# IPMC_UnderTesting.net
KiCad netlist of a schematic drawn in Altium Designer
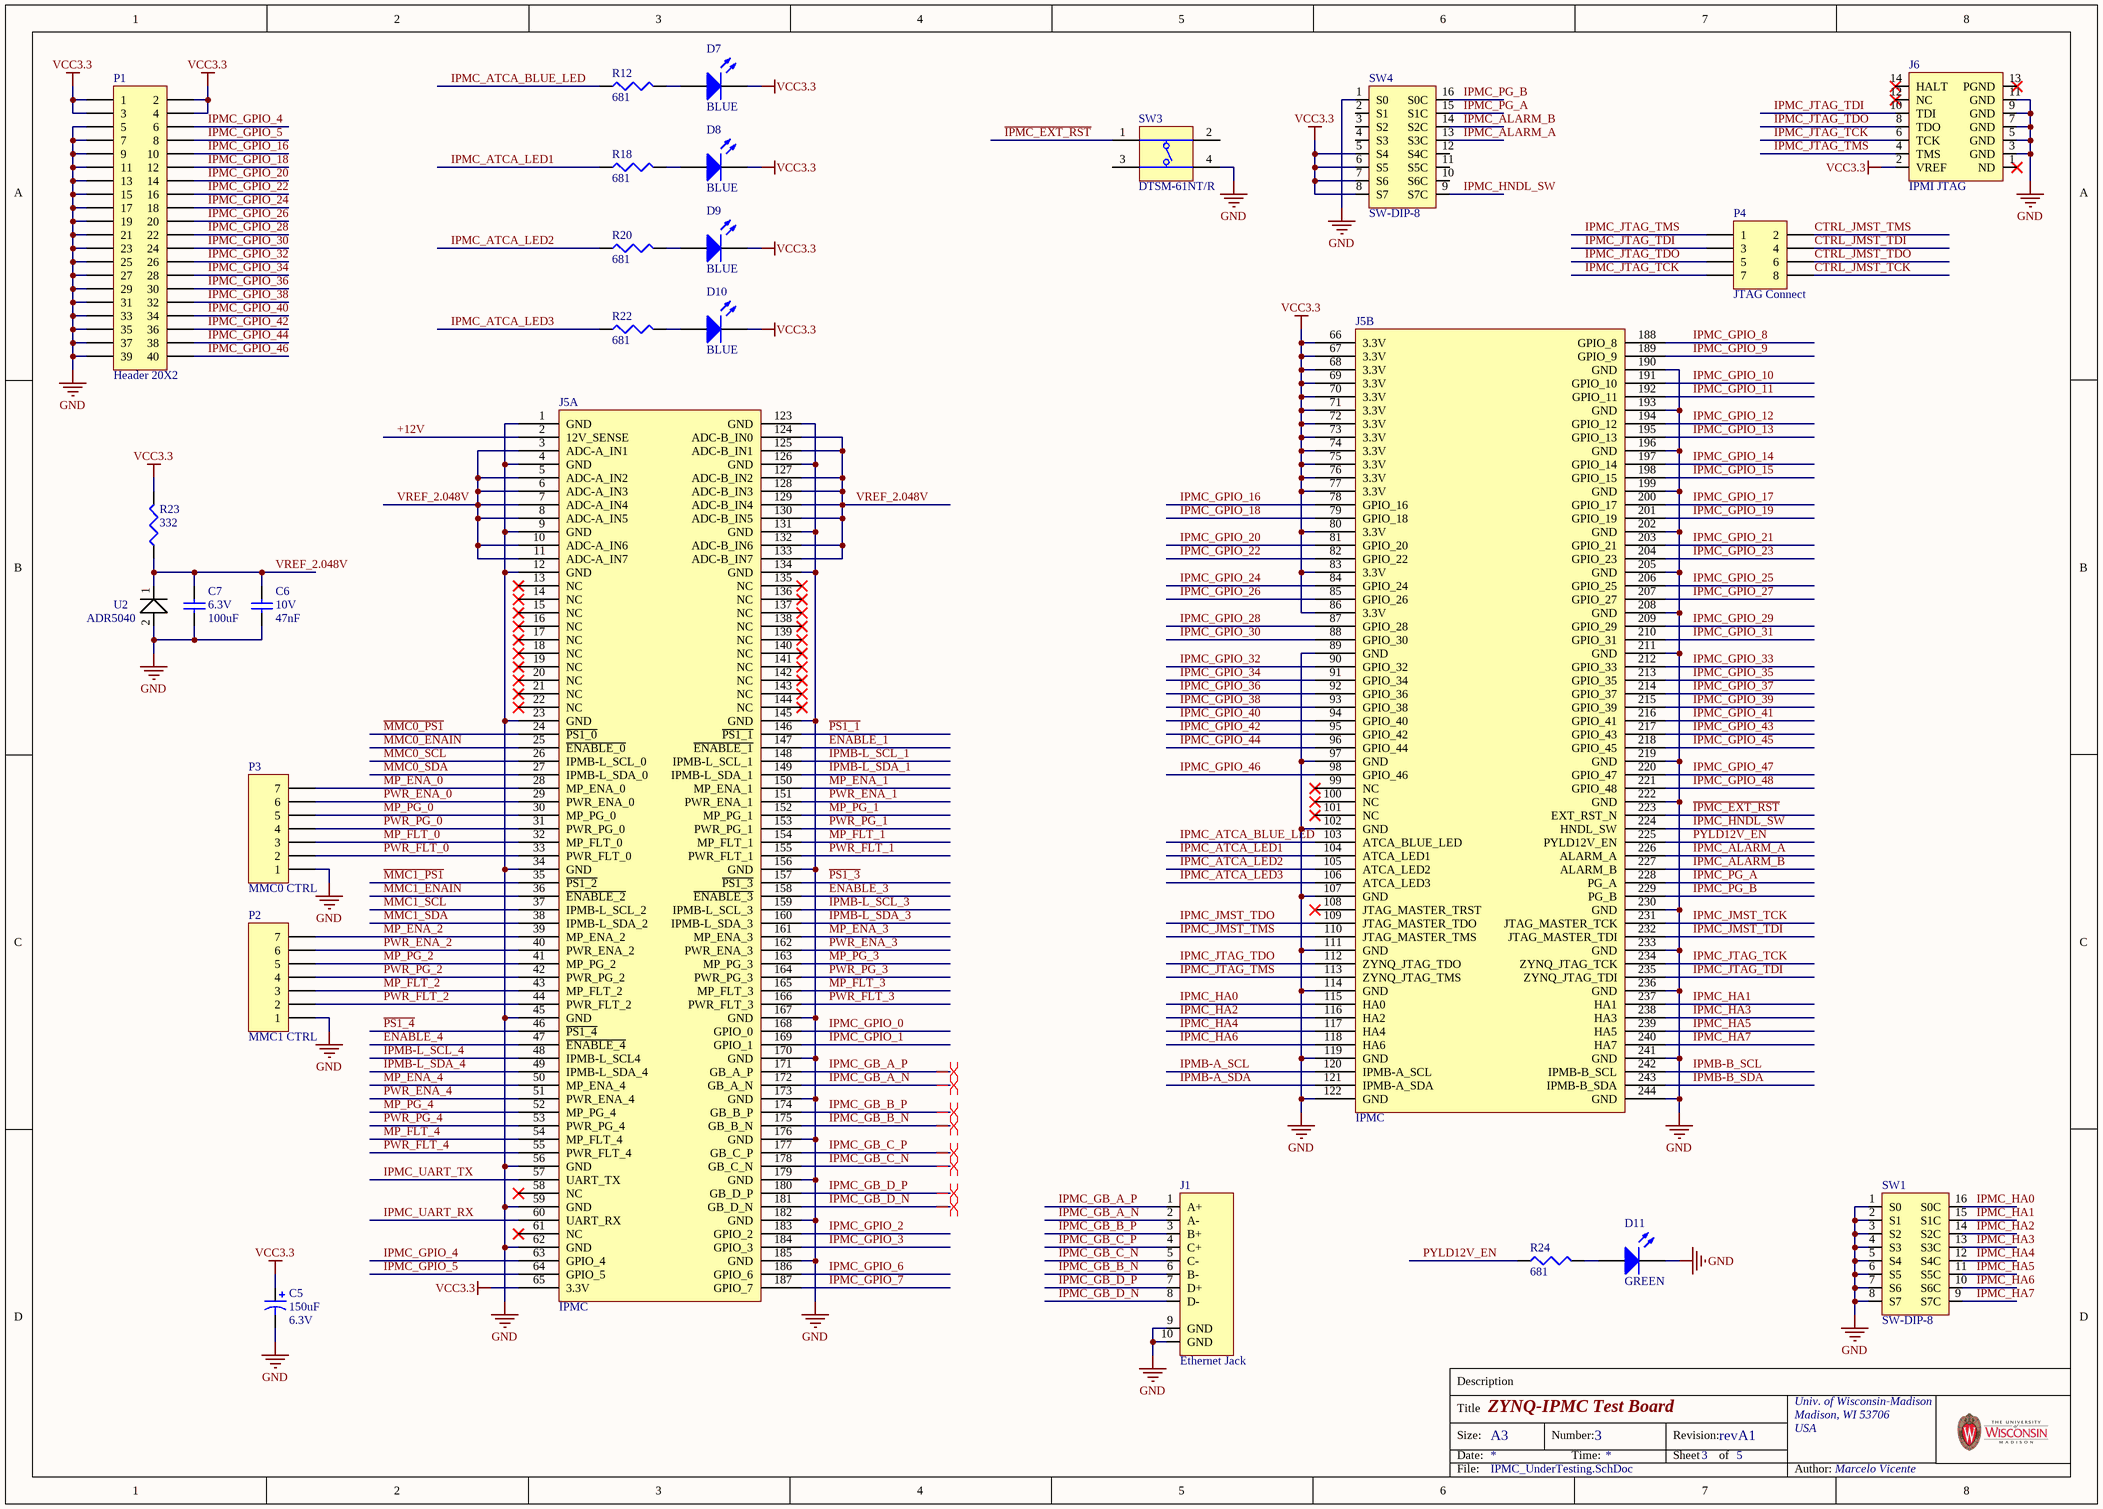
[diagram p0: IPMC_UnderTesting.SchDoc]

(export (version "E")
  (design (tool "Eeschema 10.0.6"))
  (components
    (comp (ref "C5")
      (value "150uF")
      (footprint "VISH-293D-7343-31_V")
      (description "Polarized Capacitor (Surface Mount)")
      (fields
        (field (name "RATING") "6.3V")
        (field (name "MFG. PART NO.") "A700X157M006ATE015")
        (field (name "Comment") "?")
      )
      (libsource (lib "Miscellaneous Devices") (part "Cap Pol3"))
    )
    (comp (ref "C6")
      (value "47nF")
      (footprint "C0402_IPC_H")
      (description "Capacitor")
      (fields
        (field (name "RATING") "10V")
        (field (name "MFG. PART NO.") "ECJ-0EB1A473K")
        (field (name "Comment") "?")
      )
      (libsource (lib "CustomSymbols") (part "Cap"))
    )
    (comp (ref "C7")
      (value "100uF")
      (footprint "C1210_IPC_H")
      (description "Capacitor")
      (fields
        (field (name "RATING") "6.3V")
        (field (name "MFG. PART NO.") "GRM32ER60J107ME20L")
        (field (name "Comment") "?")
      )
      (libsource (lib "CustomSymbols") (part "Cap"))
    )
    (comp (ref "D7")
      (value "BLUE")
      (footprint "LED0603_M")
      (description "Light Emitting Diode")
      (fields (field (name "MFG. PART NO.") "LTST-S270TBKT"))
      (libsource (lib "CustomSymbols") (part "LED"))
    )
    (comp (ref "D8")
      (value "BLUE")
      (footprint "LED0603_M")
      (description "Light Emitting Diode")
      (fields (field (name "MFG. PART NO.") "LTST-S270TBKT"))
      (libsource (lib "CustomSymbols") (part "LED"))
    )
    (comp (ref "D9")
      (value "BLUE")
      (footprint "LED0603_M")
      (description "Light Emitting Diode")
      (fields (field (name "MFG. PART NO.") "LTST-S270TBKT"))
      (libsource (lib "CustomSymbols") (part "LED"))
    )
    (comp (ref "D10")
      (value "BLUE")
      (footprint "LED0603_M")
      (description "Light Emitting Diode")
      (fields (field (name "MFG. PART NO.") "LTST-S270TBKT"))
      (libsource (lib "CustomSymbols") (part "LED"))
    )
    (comp (ref "D11")
      (value "GREEN")
      (footprint "LED0603_M")
      (description "Light Emitting Diode")
      (fields (field (name "MFG. PART NO.") "LTST-S270KGKT"))
      (libsource (lib "CustomSymbols") (part "LED"))
    )
    (comp (ref "J1")
      (value "Ethernet Jack")
      (footprint "43202-8916")
      (description "RJ45 Ethernet Jack")
      (fields (field (name "MFG. PART NO.") "43202-8916"))
      (libsource (lib "CustomSymbols") (part "Ethernet Jack"))
    )
    (comp (ref "J5")
      (value "IPMC")
      (footprint "87782-3007")
      (description "Molex 87782-3007")
      (fields (field (name "MFG. PART NO.") "87782-3007"))
      (libsource (lib "CustomSymbols") (part "IPMC"))
    )
    (comp (ref "J6")
      (value "IPMI JTAG")
      (footprint "87832-1420")
      (description "Molex 87832-1420")
      (fields (field (name "MFG. PART NO.") "87832-1420"))
      (libsource (lib "CustomSymbols") (part "Xilinx JTAG Header"))
    )
    (comp (ref "P1")
      (value "Header 20X2")
      (footprint "HEADER2X20")
      (description "Header, 20-Pin, Dual row")
      (fields (field (name "MFG. PART NO.") "?"))
      (libsource (lib "Miscellaneous Connectors") (part "Header 20X2"))
    )
    (comp (ref "P2")
      (value "MMC1 CTRL")
      (footprint "HEADER1X7")
      (description "Header, 7-Pin")
      (fields (field (name "MFG. PART NO.") "?"))
      (libsource (lib "Miscellaneous Connectors") (part "Header 7"))
    )
    (comp (ref "P3")
      (value "MMC0 CTRL")
      (footprint "HEADER1X7")
      (description "Header, 7-Pin")
      (fields (field (name "MFG. PART NO.") "?"))
      (libsource (lib "Miscellaneous Connectors") (part "Header 7"))
    )
    (comp (ref "P4")
      (value "JTAG Connect")
      (footprint "HEADER2X4")
      (description "Header, 4-Pin, Dual row")
      (fields (field (name "MFG. PART NO.") "?"))
      (libsource (lib "Miscellaneous Connectors") (part "Header 4X2"))
    )
    (comp (ref "R12")
      (value "681")
      (footprint "R0603")
      (description "Resistor")
      (fields (field (name "TOLERANCE") "1%") (field (name "MFG. PART NO.") "RC0603FR-07681RL"))
      (libsource (lib "CustomSymbols") (part "Res"))
    )
    (comp (ref "R18")
      (value "681")
      (footprint "R0603")
      (description "Resistor")
      (fields (field (name "TOLERANCE") "1%") (field (name "MFG. PART NO.") "RC0603FR-07681RL"))
      (libsource (lib "CustomSymbols") (part "Res"))
    )
    (comp (ref "R20")
      (value "681")
      (footprint "R0603")
      (description "Resistor")
      (fields (field (name "TOLERANCE") "1%") (field (name "MFG. PART NO.") "RC0603FR-07681RL"))
      (libsource (lib "CustomSymbols") (part "Res"))
    )
    (comp (ref "R22")
      (value "681")
      (footprint "R0603")
      (description "Resistor")
      (fields (field (name "TOLERANCE") "1%") (field (name "MFG. PART NO.") "RC0603FR-07681RL"))
      (libsource (lib "CustomSymbols") (part "Res"))
    )
    (comp (ref "R23")
      (value "332")
      (footprint "R0402_IPC_H")
      (description "Resistor")
      (fields (field (name "TOLERANCE") "1%") (field (name "MFG. PART NO.") "?"))
      (libsource (lib "CustomSymbols") (part "Res"))
    )
    (comp (ref "R24")
      (value "681")
      (footprint "R0603")
      (description "Resistor")
      (fields (field (name "TOLERANCE") "1%") (field (name "MFG. PART NO.") "RC0603FR-07681RL"))
      (libsource (lib "CustomSymbols") (part "Res"))
    )
    (comp (ref "SW1")
      (value "SW-DIP-8")
      (footprint "TDA08H0")
      (description "C&K TDA08H0SB1R")
      (fields (field (name "MFG. PART NO.") "TDA08HOSB1"))
      (libsource (lib "CustomSymbols") (part "SW-DIP-8"))
    )
    (comp (ref "SW3")
      (value "DTSM-61NT/R")
      (footprint "DIPT-DTSM-6_V")
      (description "Switch, SPNO Push Button SMD")
      (fields (field (name "MFG. PART NO.") "?"))
      (libsource (lib "Altium Content Vault") (part "DIPT-DTSM-6"))
    )
    (comp (ref "SW4")
      (value "SW-DIP-8")
      (footprint "TDA08H0")
      (description "C&K TDA08H0SB1R")
      (fields (field (name "MFG. PART NO.") "TDA08HOSB1"))
      (libsource (lib "CustomSymbols") (part "SW-DIP-8"))
    )
    (comp (ref "U2")
      (value "ADR5040")
      (footprint "SOT23-H")
      (description "Precision Micropower Shunt Mode")
      (fields (field (name "MFG. PART NO.") "ADR5040ARTZ"))
      (libsource (lib "CustomSymbols") (part "ADR5040"))
    )
  )
  (nets
    (net (code "1") (name "/+12V") (class "Default")
      (node (ref "J5") (pin "2") (pinfunction "12V_SENSE_2") (pintype "passive"))
    )
    (net (code "2") (name "/CTRL_JMST_TCK") (class "Default")
      (node (ref "P4") (pin "8") (pinfunction "8_8") (pintype "passive"))
    )
    (net (code "3") (name "/CTRL_JMST_TDI") (class "Default")
      (node (ref "P4") (pin "4") (pinfunction "4_4") (pintype "passive"))
    )
    (net (code "4") (name "/CTRL_JMST_TDO") (class "Default")
      (node (ref "P4") (pin "6") (pinfunction "6_6") (pintype "passive"))
    )
    (net (code "5") (name "/CTRL_JMST_TMS") (class "Default")
      (node (ref "P4") (pin "2") (pinfunction "2_2") (pintype "passive"))
    )
    (net (code "6") (name "/ENABLE_1") (class "Default")
      (node (ref "J5") (pin "147") (pinfunction "ENABLE_1_147") (pintype "passive"))
    )
    (net (code "7") (name "/ENABLE_3") (class "Default")
      (node (ref "J5") (pin "158") (pinfunction "ENABLE_3_158") (pintype "passive"))
    )
    (net (code "8") (name "/ENABLE_4") (class "Default")
      (node (ref "J5") (pin "47") (pinfunction "ENABLE_4_47") (pintype "passive"))
    )
    (net (code "9") (name "/IPMB-A_SCL") (class "Default")
      (node (ref "J5") (pin "120") (pinfunction "IPMB-A_SCL_120") (pintype "passive"))
    )
    (net (code "10") (name "/IPMB-A_SDA") (class "Default")
      (node (ref "J5") (pin "121") (pinfunction "IPMB-A_SDA_121") (pintype "passive"))
    )
    (net (code "11") (name "/IPMB-B_SCL") (class "Default")
      (node (ref "J5") (pin "242") (pinfunction "IPMB-B_SCL_242") (pintype "passive"))
    )
    (net (code "12") (name "/IPMB-B_SDA") (class "Default")
      (node (ref "J5") (pin "243") (pinfunction "IPMB-B_SDA_243") (pintype "passive"))
    )
    (net (code "13") (name "/IPMB-L_SCL_1") (class "Default")
      (node (ref "J5") (pin "148") (pinfunction "IPMB-L_SCL_1_148") (pintype "passive"))
    )
    (net (code "14") (name "/IPMB-L_SCL_3") (class "Default")
      (node (ref "J5") (pin "159") (pinfunction "IPMB-L_SCL_3_159") (pintype "passive"))
    )
    (net (code "15") (name "/IPMB-L_SCL_4") (class "Default")
      (node (ref "J5") (pin "48") (pinfunction "IPMB-L_SCL4_48") (pintype "passive"))
    )
    (net (code "16") (name "/IPMB-L_SDA_1") (class "Default")
      (node (ref "J5") (pin "149") (pinfunction "IPMB-L_SDA_1_149") (pintype "passive"))
    )
    (net (code "17") (name "/IPMB-L_SDA_3") (class "Default")
      (node (ref "J5") (pin "160") (pinfunction "IPMB-L_SDA_3_160") (pintype "passive"))
    )
    (net (code "18") (name "/IPMB-L_SDA_4") (class "Default")
      (node (ref "J5") (pin "49") (pinfunction "IPMB-L_SDA_4_49") (pintype "passive"))
    )
    (net (code "19") (name "/IPMC_ALARM_A") (class "Default")
      (node (ref "J5") (pin "226") (pinfunction "ALARM_A_226") (pintype "passive"))
      (node (ref "SW4") (pin "13") (pinfunction "S3C_13") (pintype "passive"))
    )
    (net (code "20") (name "/IPMC_ALARM_B") (class "Default")
      (node (ref "J5") (pin "227") (pinfunction "ALARM_B_227") (pintype "passive"))
      (node (ref "SW4") (pin "14") (pinfunction "S2C_14") (pintype "passive"))
    )
    (net (code "21") (name "/IPMC_ATCA_BLUE_LED") (class "Default")
      (node (ref "J5") (pin "103") (pinfunction "ATCA_BLUE_LED_103") (pintype "passive"))
      (node (ref "R12") (pin "1") (pinfunction "1_1") (pintype "passive"))
    )
    (net (code "22") (name "/IPMC_ATCA_LED1") (class "Default")
      (node (ref "J5") (pin "104") (pinfunction "ATCA_LED1_104") (pintype "passive"))
      (node (ref "R18") (pin "1") (pinfunction "1_1") (pintype "passive"))
    )
    (net (code "23") (name "/IPMC_ATCA_LED2") (class "Default")
      (node (ref "J5") (pin "105") (pinfunction "ATCA_LED2_105") (pintype "passive"))
      (node (ref "R20") (pin "1") (pinfunction "1_1") (pintype "passive"))
    )
    (net (code "24") (name "/IPMC_ATCA_LED3") (class "Default")
      (node (ref "J5") (pin "106") (pinfunction "ATCA_LED3_106") (pintype "passive"))
      (node (ref "R22") (pin "1") (pinfunction "1_1") (pintype "passive"))
    )
    (net (code "25") (name "/IPMC_EXT_RST") (class "Default")
      (node (ref "J5") (pin "223") (pinfunction "EXT_RST_N_223") (pintype "passive"))
      (node (ref "SW3") (pin "1") (pinfunction "T1_1") (pintype "passive"))
    )
    (net (code "26") (name "/IPMC_GB_A_N") (class "Default")
      (node (ref "J1") (pin "2") (pinfunction "A-_2") (pintype "passive"))
      (node (ref "J5") (pin "172") (pinfunction "GB_A_N_172") (pintype "passive"))
    )
    (net (code "27") (name "/IPMC_GB_A_P") (class "Default")
      (node (ref "J1") (pin "1") (pinfunction "A+_1") (pintype "passive"))
      (node (ref "J5") (pin "171") (pinfunction "GB_A_P_171") (pintype "passive"))
    )
    (net (code "28") (name "/IPMC_GB_B_N") (class "Default")
      (node (ref "J1") (pin "6") (pinfunction "B-_6") (pintype "passive"))
      (node (ref "J5") (pin "175") (pinfunction "GB_B_N_175") (pintype "passive"))
    )
    (net (code "29") (name "/IPMC_GB_B_P") (class "Default")
      (node (ref "J1") (pin "3") (pinfunction "B+_3") (pintype "passive"))
      (node (ref "J5") (pin "174") (pinfunction "GB_B_P_174") (pintype "passive"))
    )
    (net (code "30") (name "/IPMC_GB_C_N") (class "Default")
      (node (ref "J1") (pin "5") (pinfunction "C-_5") (pintype "passive"))
      (node (ref "J5") (pin "178") (pinfunction "GB_C_N_178") (pintype "passive"))
    )
    (net (code "31") (name "/IPMC_GB_C_P") (class "Default")
      (node (ref "J1") (pin "4") (pinfunction "C+_4") (pintype "passive"))
      (node (ref "J5") (pin "177") (pinfunction "GB_C_P_177") (pintype "passive"))
    )
    (net (code "32") (name "/IPMC_GB_D_N") (class "Default")
      (node (ref "J1") (pin "8") (pinfunction "D-_8") (pintype "passive"))
      (node (ref "J5") (pin "181") (pinfunction "GB_D_N_181") (pintype "passive"))
    )
    (net (code "33") (name "/IPMC_GB_D_P") (class "Default")
      (node (ref "J1") (pin "7") (pinfunction "D+_7") (pintype "passive"))
      (node (ref "J5") (pin "180") (pinfunction "GB_D_P_180") (pintype "passive"))
    )
    (net (code "34") (name "/IPMC_GPIO_0") (class "Default")
      (node (ref "J5") (pin "168") (pinfunction "GPIO_0_168") (pintype "passive"))
    )
    (net (code "35") (name "/IPMC_GPIO_1") (class "Default")
      (node (ref "J5") (pin "169") (pinfunction "GPIO_1_169") (pintype "passive"))
    )
    (net (code "36") (name "/IPMC_GPIO_2") (class "Default")
      (node (ref "J5") (pin "183") (pinfunction "GPIO_2_183") (pintype "passive"))
    )
    (net (code "37") (name "/IPMC_GPIO_3") (class "Default")
      (node (ref "J5") (pin "184") (pinfunction "GPIO_3_184") (pintype "passive"))
    )
    (net (code "38") (name "/IPMC_GPIO_4") (class "Default")
      (node (ref "J5") (pin "63") (pinfunction "GPIO_4_63") (pintype "passive"))
      (node (ref "P1") (pin "6") (pinfunction "6_6") (pintype "passive"))
    )
    (net (code "39") (name "/IPMC_GPIO_5") (class "Default")
      (node (ref "J5") (pin "64") (pinfunction "GPIO_5_64") (pintype "passive"))
      (node (ref "P1") (pin "8") (pinfunction "8_8") (pintype "passive"))
    )
    (net (code "40") (name "/IPMC_GPIO_6") (class "Default")
      (node (ref "J5") (pin "186") (pinfunction "GPIO_6_186") (pintype "passive"))
    )
    (net (code "41") (name "/IPMC_GPIO_7") (class "Default")
      (node (ref "J5") (pin "187") (pinfunction "GPIO_7_187") (pintype "passive"))
    )
    (net (code "42") (name "/IPMC_GPIO_8") (class "Default")
      (node (ref "J5") (pin "188") (pinfunction "GPIO_8_188") (pintype "passive"))
    )
    (net (code "43") (name "/IPMC_GPIO_9") (class "Default")
      (node (ref "J5") (pin "189") (pinfunction "GPIO_9_189") (pintype "passive"))
    )
    (net (code "44") (name "/IPMC_GPIO_10") (class "Default")
      (node (ref "J5") (pin "191") (pinfunction "GPIO_10_191") (pintype "passive"))
    )
    (net (code "45") (name "/IPMC_GPIO_11") (class "Default")
      (node (ref "J5") (pin "192") (pinfunction "GPIO_11_192") (pintype "passive"))
    )
    (net (code "46") (name "/IPMC_GPIO_12") (class "Default")
      (node (ref "J5") (pin "194") (pinfunction "GPIO_12_194") (pintype "passive"))
    )
    (net (code "47") (name "/IPMC_GPIO_13") (class "Default")
      (node (ref "J5") (pin "195") (pinfunction "GPIO_13_195") (pintype "passive"))
    )
    (net (code "48") (name "/IPMC_GPIO_14") (class "Default")
      (node (ref "J5") (pin "197") (pinfunction "GPIO_14_197") (pintype "passive"))
    )
    (net (code "49") (name "/IPMC_GPIO_15") (class "Default")
      (node (ref "J5") (pin "198") (pinfunction "GPIO_15_198") (pintype "passive"))
    )
    (net (code "50") (name "/IPMC_GPIO_16") (class "Default")
      (node (ref "J5") (pin "78") (pinfunction "GPIO_16_78") (pintype "passive"))
      (node (ref "P1") (pin "10") (pinfunction "10_10") (pintype "passive"))
    )
    (net (code "51") (name "/IPMC_GPIO_17") (class "Default")
      (node (ref "J5") (pin "200") (pinfunction "GPIO_17_200") (pintype "passive"))
    )
    (net (code "52") (name "/IPMC_GPIO_18") (class "Default")
      (node (ref "J5") (pin "79") (pinfunction "GPIO_18_79") (pintype "passive"))
      (node (ref "P1") (pin "12") (pinfunction "12_12") (pintype "passive"))
    )
    (net (code "53") (name "/IPMC_GPIO_19") (class "Default")
      (node (ref "J5") (pin "201") (pinfunction "GPIO_19_201") (pintype "passive"))
    )
    (net (code "54") (name "/IPMC_GPIO_20") (class "Default")
      (node (ref "J5") (pin "81") (pinfunction "GPIO_20_81") (pintype "passive"))
      (node (ref "P1") (pin "14") (pinfunction "14_14") (pintype "passive"))
    )
    (net (code "55") (name "/IPMC_GPIO_21") (class "Default")
      (node (ref "J5") (pin "203") (pinfunction "GPIO_21_203") (pintype "passive"))
    )
    (net (code "56") (name "/IPMC_GPIO_22") (class "Default")
      (node (ref "J5") (pin "82") (pinfunction "GPIO_22_82") (pintype "passive"))
      (node (ref "P1") (pin "16") (pinfunction "16_16") (pintype "passive"))
    )
    (net (code "57") (name "/IPMC_GPIO_23") (class "Default")
      (node (ref "J5") (pin "204") (pinfunction "GPIO_23_204") (pintype "passive"))
    )
    (net (code "58") (name "/IPMC_GPIO_24") (class "Default")
      (node (ref "J5") (pin "84") (pinfunction "GPIO_24_84") (pintype "passive"))
      (node (ref "P1") (pin "18") (pinfunction "18_18") (pintype "passive"))
    )
    (net (code "59") (name "/IPMC_GPIO_25") (class "Default")
      (node (ref "J5") (pin "206") (pinfunction "GPIO_25_206") (pintype "passive"))
    )
    (net (code "60") (name "/IPMC_GPIO_26") (class "Default")
      (node (ref "J5") (pin "85") (pinfunction "GPIO_26_85") (pintype "passive"))
      (node (ref "P1") (pin "20") (pinfunction "20_20") (pintype "passive"))
    )
    (net (code "61") (name "/IPMC_GPIO_27") (class "Default")
      (node (ref "J5") (pin "207") (pinfunction "GPIO_27_207") (pintype "passive"))
    )
    (net (code "62") (name "/IPMC_GPIO_28") (class "Default")
      (node (ref "J5") (pin "87") (pinfunction "GPIO_28_87") (pintype "passive"))
      (node (ref "P1") (pin "22") (pinfunction "22_22") (pintype "passive"))
    )
    (net (code "63") (name "/IPMC_GPIO_29") (class "Default")
      (node (ref "J5") (pin "209") (pinfunction "GPIO_29_209") (pintype "passive"))
    )
    (net (code "64") (name "/IPMC_GPIO_30") (class "Default")
      (node (ref "J5") (pin "88") (pinfunction "GPIO_30_88") (pintype "passive"))
      (node (ref "P1") (pin "24") (pinfunction "24_24") (pintype "passive"))
    )
    (net (code "65") (name "/IPMC_GPIO_31") (class "Default")
      (node (ref "J5") (pin "210") (pinfunction "GPIO_31_210") (pintype "passive"))
    )
    (net (code "66") (name "/IPMC_GPIO_32") (class "Default")
      (node (ref "J5") (pin "90") (pinfunction "GPIO_32_90") (pintype "passive"))
      (node (ref "P1") (pin "26") (pinfunction "26_26") (pintype "passive"))
    )
    (net (code "67") (name "/IPMC_GPIO_33") (class "Default")
      (node (ref "J5") (pin "212") (pinfunction "GPIO_33_212") (pintype "passive"))
    )
    (net (code "68") (name "/IPMC_GPIO_34") (class "Default")
      (node (ref "J5") (pin "91") (pinfunction "GPIO_34_91") (pintype "passive"))
      (node (ref "P1") (pin "28") (pinfunction "28_28") (pintype "passive"))
    )
    (net (code "69") (name "/IPMC_GPIO_35") (class "Default")
      (node (ref "J5") (pin "213") (pinfunction "GPIO_35_213") (pintype "passive"))
    )
    (net (code "70") (name "/IPMC_GPIO_36") (class "Default")
      (node (ref "J5") (pin "92") (pinfunction "GPIO_36_92") (pintype "passive"))
      (node (ref "P1") (pin "30") (pinfunction "30_30") (pintype "passive"))
    )
    (net (code "71") (name "/IPMC_GPIO_37") (class "Default")
      (node (ref "J5") (pin "214") (pinfunction "GPIO_37_214") (pintype "passive"))
    )
    (net (code "72") (name "/IPMC_GPIO_38") (class "Default")
      (node (ref "J5") (pin "93") (pinfunction "GPIO_38_93") (pintype "passive"))
      (node (ref "P1") (pin "32") (pinfunction "32_32") (pintype "passive"))
    )
    (net (code "73") (name "/IPMC_GPIO_39") (class "Default")
      (node (ref "J5") (pin "215") (pinfunction "GPIO_39_215") (pintype "passive"))
    )
    (net (code "74") (name "/IPMC_GPIO_40") (class "Default")
      (node (ref "J5") (pin "94") (pinfunction "GPIO_40_94") (pintype "passive"))
      (node (ref "P1") (pin "34") (pinfunction "34_34") (pintype "passive"))
    )
    (net (code "75") (name "/IPMC_GPIO_41") (class "Default")
      (node (ref "J5") (pin "216") (pinfunction "GPIO_41_216") (pintype "passive"))
    )
    (net (code "76") (name "/IPMC_GPIO_42") (class "Default")
      (node (ref "J5") (pin "95") (pinfunction "GPIO_42_95") (pintype "passive"))
      (node (ref "P1") (pin "36") (pinfunction "36_36") (pintype "passive"))
    )
    (net (code "77") (name "/IPMC_GPIO_43") (class "Default")
      (node (ref "J5") (pin "217") (pinfunction "GPIO_43_217") (pintype "passive"))
    )
    (net (code "78") (name "/IPMC_GPIO_44") (class "Default")
      (node (ref "J5") (pin "96") (pinfunction "GPIO_44_96") (pintype "passive"))
      (node (ref "P1") (pin "38") (pinfunction "38_38") (pintype "passive"))
    )
    (net (code "79") (name "/IPMC_GPIO_45") (class "Default")
      (node (ref "J5") (pin "218") (pinfunction "GPIO_45_218") (pintype "passive"))
    )
    (net (code "80") (name "/IPMC_GPIO_46") (class "Default")
      (node (ref "J5") (pin "98") (pinfunction "GPIO_46_98") (pintype "passive"))
      (node (ref "P1") (pin "40") (pinfunction "40_40") (pintype "passive"))
    )
    (net (code "81") (name "/IPMC_GPIO_47") (class "Default")
      (node (ref "J5") (pin "220") (pinfunction "GPIO_47_220") (pintype "passive"))
    )
    (net (code "82") (name "/IPMC_GPIO_48") (class "Default")
      (node (ref "J5") (pin "221") (pinfunction "GPIO_48_221") (pintype "passive"))
    )
    (net (code "83") (name "/IPMC_HA0") (class "Default")
      (node (ref "J5") (pin "115") (pinfunction "HA0_115") (pintype "passive"))
      (node (ref "SW1") (pin "16") (pinfunction "S0C_16") (pintype "passive"))
    )
    (net (code "84") (name "/IPMC_HA1") (class "Default")
      (node (ref "J5") (pin "237") (pinfunction "HA1_237") (pintype "passive"))
      (node (ref "SW1") (pin "15") (pinfunction "S1C_15") (pintype "passive"))
    )
    (net (code "85") (name "/IPMC_HA2") (class "Default")
      (node (ref "J5") (pin "116") (pinfunction "HA2_116") (pintype "passive"))
      (node (ref "SW1") (pin "14") (pinfunction "S2C_14") (pintype "passive"))
    )
    (net (code "86") (name "/IPMC_HA3") (class "Default")
      (node (ref "J5") (pin "238") (pinfunction "HA3_238") (pintype "passive"))
      (node (ref "SW1") (pin "13") (pinfunction "S3C_13") (pintype "passive"))
    )
    (net (code "87") (name "/IPMC_HA4") (class "Default")
      (node (ref "J5") (pin "117") (pinfunction "HA4_117") (pintype "passive"))
      (node (ref "SW1") (pin "12") (pinfunction "S4C_12") (pintype "passive"))
    )
    (net (code "88") (name "/IPMC_HA5") (class "Default")
      (node (ref "J5") (pin "239") (pinfunction "HA5_239") (pintype "passive"))
      (node (ref "SW1") (pin "11") (pinfunction "S5C_11") (pintype "passive"))
    )
    (net (code "89") (name "/IPMC_HA6") (class "Default")
      (node (ref "J5") (pin "118") (pinfunction "HA6_118") (pintype "passive"))
      (node (ref "SW1") (pin "10") (pinfunction "S6C_10") (pintype "passive"))
    )
    (net (code "90") (name "/IPMC_HA7") (class "Default")
      (node (ref "J5") (pin "240") (pinfunction "HA7_240") (pintype "passive"))
      (node (ref "SW1") (pin "9") (pinfunction "S7C_9") (pintype "passive"))
    )
    (net (code "91") (name "/IPMC_HNDL_SW") (class "Default")
      (node (ref "J5") (pin "224") (pinfunction "HNDL_SW_224") (pintype "passive"))
      (node (ref "SW4") (pin "9") (pinfunction "S7C_9") (pintype "passive"))
    )
    (net (code "92") (name "/IPMC_JMST_TCK") (class "Default")
      (node (ref "J5") (pin "231") (pinfunction "JTAG_MASTER_TCK_231") (pintype "passive"))
    )
    (net (code "93") (name "/IPMC_JMST_TDI") (class "Default")
      (node (ref "J5") (pin "232") (pinfunction "JTAG_MASTER_TDI_232") (pintype "passive"))
    )
    (net (code "94") (name "/IPMC_JMST_TDO") (class "Default")
      (node (ref "J5") (pin "109") (pinfunction "JTAG_MASTER_TDO_109") (pintype "passive"))
    )
    (net (code "95") (name "/IPMC_JMST_TMS") (class "Default")
      (node (ref "J5") (pin "110") (pinfunction "JTAG_MASTER_TMS_110") (pintype "passive"))
    )
    (net (code "96") (name "/IPMC_JTAG_TCK") (class "Default")
      (node (ref "J5") (pin "234") (pinfunction "ZYNQ_JTAG_TCK_234") (pintype "passive"))
      (node (ref "J6") (pin "6") (pinfunction "TCK_6") (pintype "passive"))
      (node (ref "P4") (pin "7") (pinfunction "7_7") (pintype "passive"))
    )
    (net (code "97") (name "/IPMC_JTAG_TDI") (class "Default")
      (node (ref "J5") (pin "235") (pinfunction "ZYNQ_JTAG_TDI_235") (pintype "passive"))
      (node (ref "J6") (pin "10") (pinfunction "TDI_10") (pintype "passive"))
      (node (ref "P4") (pin "3") (pinfunction "3_3") (pintype "passive"))
    )
    (net (code "98") (name "/IPMC_JTAG_TDO") (class "Default")
      (node (ref "J5") (pin "112") (pinfunction "ZYNQ_JTAG_TDO_112") (pintype "passive"))
      (node (ref "J6") (pin "8") (pinfunction "TDO_8") (pintype "passive"))
      (node (ref "P4") (pin "5") (pinfunction "5_5") (pintype "passive"))
    )
    (net (code "99") (name "/IPMC_JTAG_TMS") (class "Default")
      (node (ref "J5") (pin "113") (pinfunction "ZYNQ_JTAG_TMS_113") (pintype "passive"))
      (node (ref "J6") (pin "4") (pinfunction "TMS_4") (pintype "passive"))
      (node (ref "P4") (pin "1") (pinfunction "1_1") (pintype "passive"))
    )
    (net (code "100") (name "/IPMC_PG_A") (class "Default")
      (node (ref "J5") (pin "228") (pinfunction "PG_A_228") (pintype "passive"))
      (node (ref "SW4") (pin "15") (pinfunction "S1C_15") (pintype "passive"))
    )
    (net (code "101") (name "/IPMC_PG_B") (class "Default")
      (node (ref "J5") (pin "229") (pinfunction "PG_B_229") (pintype "passive"))
      (node (ref "SW4") (pin "16") (pinfunction "S0C_16") (pintype "passive"))
    )
    (net (code "102") (name "/IPMC_UART_RX") (class "Default")
      (node (ref "J5") (pin "60") (pinfunction "UART_RX_60") (pintype "passive"))
    )
    (net (code "103") (name "/IPMC_UART_TX") (class "Default")
      (node (ref "J5") (pin "57") (pinfunction "UART_TX_57") (pintype "passive"))
    )
    (net (code "104") (name "/MMC0_ENAIN") (class "Default")
      (node (ref "J5") (pin "25") (pinfunction "ENABLE_0_25") (pintype "passive"))
    )
    (net (code "105") (name "/MMC0_PS1") (class "Default")
      (node (ref "J5") (pin "24") (pinfunction "PS1_0_24") (pintype "passive"))
    )
    (net (code "106") (name "/MMC0_SCL") (class "Default")
      (node (ref "J5") (pin "26") (pinfunction "IPMB-L_SCL_0_26") (pintype "passive"))
    )
    (net (code "107") (name "/MMC0_SDA") (class "Default")
      (node (ref "J5") (pin "27") (pinfunction "IPMB-L_SDA_0_27") (pintype "passive"))
    )
    (net (code "108") (name "/MMC1_ENAIN") (class "Default")
      (node (ref "J5") (pin "36") (pinfunction "ENABLE_2_36") (pintype "passive"))
    )
    (net (code "109") (name "/MMC1_PS1") (class "Default")
      (node (ref "J5") (pin "35") (pinfunction "PS1_2_35") (pintype "passive"))
    )
    (net (code "110") (name "/MMC1_SCL") (class "Default")
      (node (ref "J5") (pin "37") (pinfunction "IPMB-L_SCL_2_37") (pintype "passive"))
    )
    (net (code "111") (name "/MMC1_SDA") (class "Default")
      (node (ref "J5") (pin "38") (pinfunction "IPMB-L_SDA_2_38") (pintype "passive"))
    )
    (net (code "112") (name "/MP_ENA_0") (class "Default")
      (node (ref "J5") (pin "28") (pinfunction "MP_ENA_0_28") (pintype "passive"))
      (node (ref "P3") (pin "7") (pinfunction "7_7") (pintype "passive"))
    )
    (net (code "113") (name "/MP_ENA_1") (class "Default")
      (node (ref "J5") (pin "150") (pinfunction "MP_ENA_1_150") (pintype "passive"))
    )
    (net (code "114") (name "/MP_ENA_2") (class "Default")
      (node (ref "J5") (pin "39") (pinfunction "MP_ENA_2_39") (pintype "passive"))
      (node (ref "P2") (pin "7") (pinfunction "7_7") (pintype "passive"))
    )
    (net (code "115") (name "/MP_ENA_3") (class "Default")
      (node (ref "J5") (pin "161") (pinfunction "MP_ENA_3_161") (pintype "passive"))
    )
    (net (code "116") (name "/MP_ENA_4") (class "Default")
      (node (ref "J5") (pin "50") (pinfunction "MP_ENA_4_50") (pintype "passive"))
    )
    (net (code "117") (name "/MP_FLT_0") (class "Default")
      (node (ref "J5") (pin "32") (pinfunction "MP_FLT_0_32") (pintype "passive"))
      (node (ref "P3") (pin "3") (pinfunction "3_3") (pintype "passive"))
    )
    (net (code "118") (name "/MP_FLT_1") (class "Default")
      (node (ref "J5") (pin "154") (pinfunction "MP_FLT_1_154") (pintype "passive"))
    )
    (net (code "119") (name "/MP_FLT_2") (class "Default")
      (node (ref "J5") (pin "43") (pinfunction "MP_FLT_2_43") (pintype "passive"))
      (node (ref "P2") (pin "3") (pinfunction "3_3") (pintype "passive"))
    )
    (net (code "120") (name "/MP_FLT_3") (class "Default")
      (node (ref "J5") (pin "165") (pinfunction "MP_FLT_3_165") (pintype "passive"))
    )
    (net (code "121") (name "/MP_FLT_4") (class "Default")
      (node (ref "J5") (pin "54") (pinfunction "MP_FLT_4_54") (pintype "passive"))
    )
    (net (code "122") (name "/MP_PG_0") (class "Default")
      (node (ref "J5") (pin "30") (pinfunction "MP_PG_0_30") (pintype "passive"))
      (node (ref "P3") (pin "5") (pinfunction "5_5") (pintype "passive"))
    )
    (net (code "123") (name "/MP_PG_1") (class "Default")
      (node (ref "J5") (pin "152") (pinfunction "MP_PG_1_152") (pintype "passive"))
    )
    (net (code "124") (name "/MP_PG_2") (class "Default")
      (node (ref "J5") (pin "41") (pinfunction "MP_PG_2_41") (pintype "passive"))
      (node (ref "P2") (pin "5") (pinfunction "5_5") (pintype "passive"))
    )
    (net (code "125") (name "/MP_PG_3") (class "Default")
      (node (ref "J5") (pin "163") (pinfunction "MP_PG_3_163") (pintype "passive"))
    )
    (net (code "126") (name "/MP_PG_4") (class "Default")
      (node (ref "J5") (pin "52") (pinfunction "MP_PG_4_52") (pintype "passive"))
    )
    (net (code "127") (name "/PS1_1") (class "Default")
      (node (ref "J5") (pin "146") (pinfunction "PS1_1_146") (pintype "passive"))
    )
    (net (code "128") (name "/PS1_3") (class "Default")
      (node (ref "J5") (pin "157") (pinfunction "PS1_3_157") (pintype "passive"))
    )
    (net (code "129") (name "/PS1_4") (class "Default")
      (node (ref "J5") (pin "46") (pinfunction "PS1_4_46") (pintype "passive"))
    )
    (net (code "130") (name "/PWR_ENA_0") (class "Default")
      (node (ref "J5") (pin "29") (pinfunction "PWR_ENA_0_29") (pintype "passive"))
      (node (ref "P3") (pin "6") (pinfunction "6_6") (pintype "passive"))
    )
    (net (code "131") (name "/PWR_ENA_1") (class "Default")
      (node (ref "J5") (pin "151") (pinfunction "PWR_ENA_1_151") (pintype "passive"))
    )
    (net (code "132") (name "/PWR_ENA_2") (class "Default")
      (node (ref "J5") (pin "40") (pinfunction "PWR_ENA_2_40") (pintype "passive"))
      (node (ref "P2") (pin "6") (pinfunction "6_6") (pintype "passive"))
    )
    (net (code "133") (name "/PWR_ENA_3") (class "Default")
      (node (ref "J5") (pin "162") (pinfunction "PWR_ENA_3_162") (pintype "passive"))
    )
    (net (code "134") (name "/PWR_ENA_4") (class "Default")
      (node (ref "J5") (pin "51") (pinfunction "PWR_ENA_4_51") (pintype "passive"))
    )
    (net (code "135") (name "/PWR_FLT_0") (class "Default")
      (node (ref "J5") (pin "33") (pinfunction "PWR_FLT_0_33") (pintype "passive"))
      (node (ref "P3") (pin "2") (pinfunction "2_2") (pintype "passive"))
    )
    (net (code "136") (name "/PWR_FLT_1") (class "Default")
      (node (ref "J5") (pin "155") (pinfunction "PWR_FLT_1_155") (pintype "passive"))
    )
    (net (code "137") (name "/PWR_FLT_2") (class "Default")
      (node (ref "J5") (pin "44") (pinfunction "PWR_FLT_2_44") (pintype "passive"))
      (node (ref "P2") (pin "2") (pinfunction "2_2") (pintype "passive"))
    )
    (net (code "138") (name "/PWR_FLT_3") (class "Default")
      (node (ref "J5") (pin "166") (pinfunction "PWR_FLT_3_166") (pintype "passive"))
    )
    (net (code "139") (name "/PWR_FLT_4") (class "Default")
      (node (ref "J5") (pin "55") (pinfunction "PWR_FLT_4_55") (pintype "passive"))
    )
    (net (code "140") (name "/PWR_PG_0") (class "Default")
      (node (ref "J5") (pin "31") (pinfunction "PWR_PG_0_31") (pintype "passive"))
      (node (ref "P3") (pin "4") (pinfunction "4_4") (pintype "passive"))
    )
    (net (code "141") (name "/PWR_PG_1") (class "Default")
      (node (ref "J5") (pin "153") (pinfunction "PWR_PG_1_153") (pintype "passive"))
    )
    (net (code "142") (name "/PWR_PG_2") (class "Default")
      (node (ref "J5") (pin "42") (pinfunction "PWR_PG_2_42") (pintype "passive"))
      (node (ref "P2") (pin "4") (pinfunction "4_4") (pintype "passive"))
    )
    (net (code "143") (name "/PWR_PG_3") (class "Default")
      (node (ref "J5") (pin "164") (pinfunction "PWR_PG_3_164") (pintype "passive"))
    )
    (net (code "144") (name "/PWR_PG_4") (class "Default")
      (node (ref "J5") (pin "53") (pinfunction "PWR_PG_4_53") (pintype "passive"))
    )
    (net (code "145") (name "/PYLD12V_EN") (class "Default")
      (node (ref "J5") (pin "225") (pinfunction "PYLD12V_EN_225") (pintype "passive"))
      (node (ref "R24") (pin "1") (pinfunction "1_1") (pintype "passive"))
    )
    (net (code "146") (name "/VREF_2.048V") (class "Default")
      (node (ref "C6") (pin "2") (pinfunction "2_2") (pintype "passive"))
      (node (ref "C7") (pin "2") (pinfunction "2_2") (pintype "passive"))
      (node (ref "J5") (pin "10") (pinfunction "ADC-A_IN6_10") (pintype "passive"))
      (node (ref "J5") (pin "11") (pinfunction "ADC-A_IN7_11") (pintype "passive"))
      (node (ref "J5") (pin "124") (pinfunction "ADC-B_IN0_124") (pintype "passive"))
      (node (ref "J5") (pin "125") (pinfunction "ADC-B_IN1_125") (pintype "passive"))
      (node (ref "J5") (pin "127") (pinfunction "ADC-B_IN2_127") (pintype "passive"))
      (node (ref "J5") (pin "128") (pinfunction "ADC-B_IN3_128") (pintype "passive"))
      (node (ref "J5") (pin "129") (pinfunction "ADC-B_IN4_129") (pintype "passive"))
      (node (ref "J5") (pin "130") (pinfunction "ADC-B_IN5_130") (pintype "passive"))
      (node (ref "J5") (pin "132") (pinfunction "ADC-B_IN6_132") (pintype "passive"))
      (node (ref "J5") (pin "133") (pinfunction "ADC-B_IN7_133") (pintype "passive"))
      (node (ref "J5") (pin "3") (pinfunction "ADC-A_IN1_3") (pintype "passive"))
      (node (ref "J5") (pin "5") (pinfunction "ADC-A_IN2_5") (pintype "passive"))
      (node (ref "J5") (pin "6") (pinfunction "ADC-A_IN3_6") (pintype "passive"))
      (node (ref "J5") (pin "7") (pinfunction "ADC-A_IN4_7") (pintype "passive"))
      (node (ref "J5") (pin "8") (pinfunction "ADC-A_IN5_8") (pintype "passive"))
      (node (ref "R23") (pin "1") (pinfunction "1_1") (pintype "passive"))
      (node (ref "U2") (pin "1") (pinfunction "V+_1") (pintype "passive"))
    )
    (net (code "147") (name "GND") (class "Default")
      (node (ref "C5") (pin "2") (pinfunction "2_2") (pintype "passive"))
      (node (ref "C6") (pin "1") (pinfunction "1_1") (pintype "passive"))
      (node (ref "C7") (pin "1") (pinfunction "1_1") (pintype "passive"))
      (node (ref "D11") (pin "2") (pinfunction "K_2") (pintype "passive"))
      (node (ref "J1") (pin "10") (pinfunction "GND_10") (pintype "passive"))
      (node (ref "J1") (pin "9") (pinfunction "GND_9") (pintype "passive"))
      (node (ref "J5") (pin "1") (pinfunction "GND_1") (pintype "passive"))
      (node (ref "J5") (pin "102") (pinfunction "GND_102") (pintype "passive"))
      (node (ref "J5") (pin "107") (pinfunction "GND_107") (pintype "passive"))
      (node (ref "J5") (pin "111") (pinfunction "GND_111") (pintype "passive"))
      (node (ref "J5") (pin "114") (pinfunction "GND_114") (pintype "passive"))
      (node (ref "J5") (pin "119") (pinfunction "GND_119") (pintype "passive"))
      (node (ref "J5") (pin "12") (pinfunction "GND_12") (pintype "passive"))
      (node (ref "J5") (pin "122") (pinfunction "GND_122") (pintype "passive"))
      (node (ref "J5") (pin "123") (pinfunction "GND_123") (pintype "passive"))
      (node (ref "J5") (pin "126") (pinfunction "GND_126") (pintype "passive"))
      (node (ref "J5") (pin "131") (pinfunction "GND_131") (pintype "passive"))
      (node (ref "J5") (pin "134") (pinfunction "GND_134") (pintype "passive"))
      (node (ref "J5") (pin "145") (pinfunction "GND_145") (pintype "passive"))
      (node (ref "J5") (pin "156") (pinfunction "GND_156") (pintype "passive"))
      (node (ref "J5") (pin "167") (pinfunction "GND_167") (pintype "passive"))
      (node (ref "J5") (pin "170") (pinfunction "GND_170") (pintype "passive"))
      (node (ref "J5") (pin "173") (pinfunction "GND_173") (pintype "passive"))
      (node (ref "J5") (pin "176") (pinfunction "GND_176") (pintype "passive"))
      (node (ref "J5") (pin "179") (pinfunction "GND_179") (pintype "passive"))
      (node (ref "J5") (pin "182") (pinfunction "GND_182") (pintype "passive"))
      (node (ref "J5") (pin "185") (pinfunction "GND_185") (pintype "passive"))
      (node (ref "J5") (pin "190") (pinfunction "GND_190") (pintype "passive"))
      (node (ref "J5") (pin "193") (pinfunction "GND_193") (pintype "passive"))
      (node (ref "J5") (pin "196") (pinfunction "GND_196") (pintype "passive"))
      (node (ref "J5") (pin "199") (pinfunction "GND_199") (pintype "passive"))
      (node (ref "J5") (pin "202") (pinfunction "GND_202") (pintype "passive"))
      (node (ref "J5") (pin "205") (pinfunction "GND_205") (pintype "passive"))
      (node (ref "J5") (pin "208") (pinfunction "GND_208") (pintype "passive"))
      (node (ref "J5") (pin "211") (pinfunction "GND_211") (pintype "passive"))
      (node (ref "J5") (pin "219") (pinfunction "GND_219") (pintype "passive"))
      (node (ref "J5") (pin "222") (pinfunction "GND_222") (pintype "passive"))
      (node (ref "J5") (pin "23") (pinfunction "GND_23") (pintype "passive"))
      (node (ref "J5") (pin "230") (pinfunction "GND_230") (pintype "passive"))
      (node (ref "J5") (pin "233") (pinfunction "GND_233") (pintype "passive"))
      (node (ref "J5") (pin "236") (pinfunction "GND_236") (pintype "passive"))
      (node (ref "J5") (pin "241") (pinfunction "GND_241") (pintype "passive"))
      (node (ref "J5") (pin "244") (pinfunction "GND_244") (pintype "passive"))
      (node (ref "J5") (pin "34") (pinfunction "GND_34") (pintype "passive"))
      (node (ref "J5") (pin "4") (pinfunction "GND_4") (pintype "passive"))
      (node (ref "J5") (pin "45") (pinfunction "GND_45") (pintype "passive"))
      (node (ref "J5") (pin "56") (pinfunction "GND_56") (pintype "passive"))
      (node (ref "J5") (pin "59") (pinfunction "GND_59") (pintype "passive"))
      (node (ref "J5") (pin "62") (pinfunction "GND_62") (pintype "passive"))
      (node (ref "J5") (pin "89") (pinfunction "GND_89") (pintype "passive"))
      (node (ref "J5") (pin "9") (pinfunction "GND_9") (pintype "passive"))
      (node (ref "J5") (pin "97") (pinfunction "GND_97") (pintype "passive"))
      (node (ref "J6") (pin "11") (pinfunction "GND_11") (pintype "passive"))
      (node (ref "J6") (pin "3") (pinfunction "GND_3") (pintype "passive"))
      (node (ref "J6") (pin "5") (pinfunction "GND_5") (pintype "passive"))
      (node (ref "J6") (pin "7") (pinfunction "GND_7") (pintype "passive"))
      (node (ref "J6") (pin "9") (pinfunction "GND_9") (pintype "passive"))
      (node (ref "P1") (pin "11") (pinfunction "11_11") (pintype "passive"))
      (node (ref "P1") (pin "13") (pinfunction "13_13") (pintype "passive"))
      (node (ref "P1") (pin "15") (pinfunction "15_15") (pintype "passive"))
      (node (ref "P1") (pin "17") (pinfunction "17_17") (pintype "passive"))
      (node (ref "P1") (pin "19") (pinfunction "19_19") (pintype "passive"))
      (node (ref "P1") (pin "21") (pinfunction "21_21") (pintype "passive"))
      (node (ref "P1") (pin "23") (pinfunction "23_23") (pintype "passive"))
      (node (ref "P1") (pin "25") (pinfunction "25_25") (pintype "passive"))
      (node (ref "P1") (pin "27") (pinfunction "27_27") (pintype "passive"))
      (node (ref "P1") (pin "29") (pinfunction "29_29") (pintype "passive"))
      (node (ref "P1") (pin "31") (pinfunction "31_31") (pintype "passive"))
      (node (ref "P1") (pin "33") (pinfunction "33_33") (pintype "passive"))
      (node (ref "P1") (pin "35") (pinfunction "35_35") (pintype "passive"))
      (node (ref "P1") (pin "37") (pinfunction "37_37") (pintype "passive"))
      (node (ref "P1") (pin "39") (pinfunction "39_39") (pintype "passive"))
      (node (ref "P1") (pin "5") (pinfunction "5_5") (pintype "passive"))
      (node (ref "P1") (pin "7") (pinfunction "7_7") (pintype "passive"))
      (node (ref "P1") (pin "9") (pinfunction "9_9") (pintype "passive"))
      (node (ref "P2") (pin "1") (pinfunction "1_1") (pintype "passive"))
      (node (ref "P3") (pin "1") (pinfunction "1_1") (pintype "passive"))
      (node (ref "SW1") (pin "1") (pinfunction "S0_1") (pintype "passive"))
      (node (ref "SW1") (pin "2") (pinfunction "S1_2") (pintype "passive"))
      (node (ref "SW1") (pin "3") (pinfunction "S2_3") (pintype "passive"))
      (node (ref "SW1") (pin "4") (pinfunction "S3_4") (pintype "passive"))
      (node (ref "SW1") (pin "5") (pinfunction "S4_5") (pintype "passive"))
      (node (ref "SW1") (pin "6") (pinfunction "S5_6") (pintype "passive"))
      (node (ref "SW1") (pin "7") (pinfunction "S6_7") (pintype "passive"))
      (node (ref "SW1") (pin "8") (pinfunction "S7_8") (pintype "passive"))
      (node (ref "SW3") (pin "4") (pinfunction "T3_4") (pintype "passive"))
      (node (ref "SW4") (pin "1") (pinfunction "S0_1") (pintype "passive"))
      (node (ref "U2") (pin "2") (pinfunction "V+_2") (pintype "passive"))
    )
    (net (code "148") (name "Net-(D7-A)") (class "Default")
      (node (ref "D7") (pin "1") (pinfunction "A_1") (pintype "passive"))
      (node (ref "R12") (pin "2") (pinfunction "2_2") (pintype "passive"))
    )
    (net (code "149") (name "Net-(D8-A)") (class "Default")
      (node (ref "D8") (pin "1") (pinfunction "A_1") (pintype "passive"))
      (node (ref "R18") (pin "2") (pinfunction "2_2") (pintype "passive"))
    )
    (net (code "150") (name "Net-(D9-A)") (class "Default")
      (node (ref "D9") (pin "1") (pinfunction "A_1") (pintype "passive"))
      (node (ref "R20") (pin "2") (pinfunction "2_2") (pintype "passive"))
    )
    (net (code "151") (name "Net-(D10-A)") (class "Default")
      (node (ref "D10") (pin "1") (pinfunction "A_1") (pintype "passive"))
      (node (ref "R22") (pin "2") (pinfunction "2_2") (pintype "passive"))
    )
    (net (code "152") (name "Net-(D11-A)") (class "Default")
      (node (ref "D11") (pin "1") (pinfunction "A_1") (pintype "passive"))
      (node (ref "R24") (pin "2") (pinfunction "2_2") (pintype "passive"))
    )
    (net (code "153") (name "VCC3.3") (class "Default")
      (node (ref "C5") (pin "1") (pinfunction "1_1") (pintype "passive"))
      (node (ref "D10") (pin "2") (pinfunction "K_2") (pintype "passive"))
      (node (ref "D7") (pin "2") (pinfunction "K_2") (pintype "passive"))
      (node (ref "D8") (pin "2") (pinfunction "K_2") (pintype "passive"))
      (node (ref "D9") (pin "2") (pinfunction "K_2") (pintype "passive"))
      (node (ref "J5") (pin "65") (pinfunction "3.3V_65") (pintype "passive"))
      (node (ref "J5") (pin "66") (pinfunction "3.3V_66") (pintype "passive"))
      (node (ref "J5") (pin "67") (pinfunction "3.3V_67") (pintype "passive"))
      (node (ref "J5") (pin "68") (pinfunction "3.3V_68") (pintype "passive"))
      (node (ref "J5") (pin "69") (pinfunction "3.3V_69") (pintype "passive"))
      (node (ref "J5") (pin "70") (pinfunction "3.3V_70") (pintype "passive"))
      (node (ref "J5") (pin "71") (pinfunction "3.3V_71") (pintype "passive"))
      (node (ref "J5") (pin "72") (pinfunction "3.3V_72") (pintype "passive"))
      (node (ref "J5") (pin "73") (pinfunction "3.3V_73") (pintype "passive"))
      (node (ref "J5") (pin "74") (pinfunction "3.3V_74") (pintype "passive"))
      (node (ref "J5") (pin "75") (pinfunction "3.3V_75") (pintype "passive"))
      (node (ref "J5") (pin "76") (pinfunction "3.3V_76") (pintype "passive"))
      (node (ref "J5") (pin "77") (pinfunction "3.3V_77") (pintype "passive"))
      (node (ref "J5") (pin "80") (pinfunction "3.3V_80") (pintype "passive"))
      (node (ref "J5") (pin "83") (pinfunction "3.3V_83") (pintype "passive"))
      (node (ref "J5") (pin "86") (pinfunction "3.3V_86") (pintype "passive"))
      (node (ref "J6") (pin "2") (pinfunction "VREF_2") (pintype "passive"))
      (node (ref "P1") (pin "1") (pinfunction "1_1") (pintype "passive"))
      (node (ref "P1") (pin "2") (pinfunction "2_2") (pintype "passive"))
      (node (ref "P1") (pin "3") (pinfunction "3_3") (pintype "passive"))
      (node (ref "P1") (pin "4") (pinfunction "4_4") (pintype "passive"))
      (node (ref "R23") (pin "2") (pinfunction "2_2") (pintype "passive"))
      (node (ref "SW4") (pin "5") (pinfunction "S4_5") (pintype "passive"))
      (node (ref "SW4") (pin "6") (pinfunction "S5_6") (pintype "passive"))
      (node (ref "SW4") (pin "7") (pinfunction "S6_7") (pintype "passive"))
      (node (ref "SW4") (pin "8") (pinfunction "S7_8") (pintype "passive"))
    )
    (net (code "154") (name "unconnected-(J5A-NC-Pad13)") (class "Default")
      (node (ref "J5") (pin "13") (pinfunction "NC_13") (pintype "passive+no_connect"))
    )
    (net (code "155") (name "unconnected-(J5A-NC-Pad14)") (class "Default")
      (node (ref "J5") (pin "14") (pinfunction "NC_14") (pintype "passive+no_connect"))
    )
    (net (code "156") (name "unconnected-(J5A-NC-Pad15)") (class "Default")
      (node (ref "J5") (pin "15") (pinfunction "NC_15") (pintype "passive+no_connect"))
    )
    (net (code "157") (name "unconnected-(J5A-NC-Pad16)") (class "Default")
      (node (ref "J5") (pin "16") (pinfunction "NC_16") (pintype "passive+no_connect"))
    )
    (net (code "158") (name "unconnected-(J5A-NC-Pad17)") (class "Default")
      (node (ref "J5") (pin "17") (pinfunction "NC_17") (pintype "passive+no_connect"))
    )
    (net (code "159") (name "unconnected-(J5A-NC-Pad18)") (class "Default")
      (node (ref "J5") (pin "18") (pinfunction "NC_18") (pintype "passive+no_connect"))
    )
    (net (code "160") (name "unconnected-(J5A-NC-Pad19)") (class "Default")
      (node (ref "J5") (pin "19") (pinfunction "NC_19") (pintype "passive+no_connect"))
    )
    (net (code "161") (name "unconnected-(J5A-NC-Pad20)") (class "Default")
      (node (ref "J5") (pin "20") (pinfunction "NC_20") (pintype "passive+no_connect"))
    )
    (net (code "162") (name "unconnected-(J5A-NC-Pad21)") (class "Default")
      (node (ref "J5") (pin "21") (pinfunction "NC_21") (pintype "passive+no_connect"))
    )
    (net (code "163") (name "unconnected-(J5A-NC-Pad22)") (class "Default")
      (node (ref "J5") (pin "22") (pinfunction "NC_22") (pintype "passive+no_connect"))
    )
    (net (code "164") (name "unconnected-(J5A-NC-Pad58)") (class "Default")
      (node (ref "J5") (pin "58") (pinfunction "NC_58") (pintype "passive+no_connect"))
    )
    (net (code "165") (name "unconnected-(J5A-NC-Pad61)") (class "Default")
      (node (ref "J5") (pin "61") (pinfunction "NC_61") (pintype "passive+no_connect"))
    )
    (net (code "166") (name "unconnected-(J5A-NC-Pad135)") (class "Default")
      (node (ref "J5") (pin "135") (pinfunction "NC_135") (pintype "passive+no_connect"))
    )
    (net (code "167") (name "unconnected-(J5A-NC-Pad136)") (class "Default")
      (node (ref "J5") (pin "136") (pinfunction "NC_136") (pintype "passive+no_connect"))
    )
    (net (code "168") (name "unconnected-(J5A-NC-Pad137)") (class "Default")
      (node (ref "J5") (pin "137") (pinfunction "NC_137") (pintype "passive+no_connect"))
    )
    (net (code "169") (name "unconnected-(J5A-NC-Pad138)") (class "Default")
      (node (ref "J5") (pin "138") (pinfunction "NC_138") (pintype "passive+no_connect"))
    )
    (net (code "170") (name "unconnected-(J5A-NC-Pad139)") (class "Default")
      (node (ref "J5") (pin "139") (pinfunction "NC_139") (pintype "passive+no_connect"))
    )
    (net (code "171") (name "unconnected-(J5A-NC-Pad140)") (class "Default")
      (node (ref "J5") (pin "140") (pinfunction "NC_140") (pintype "passive+no_connect"))
    )
    (net (code "172") (name "unconnected-(J5A-NC-Pad141)") (class "Default")
      (node (ref "J5") (pin "141") (pinfunction "NC_141") (pintype "passive+no_connect"))
    )
    (net (code "173") (name "unconnected-(J5A-NC-Pad142)") (class "Default")
      (node (ref "J5") (pin "142") (pinfunction "NC_142") (pintype "passive+no_connect"))
    )
    (net (code "174") (name "unconnected-(J5A-NC-Pad143)") (class "Default")
      (node (ref "J5") (pin "143") (pinfunction "NC_143") (pintype "passive+no_connect"))
    )
    (net (code "175") (name "unconnected-(J5A-NC-Pad144)") (class "Default")
      (node (ref "J5") (pin "144") (pinfunction "NC_144") (pintype "passive+no_connect"))
    )
    (net (code "176") (name "unconnected-(J5B-JTAG_MASTER_TRST-Pad108)") (class "Default")
      (node (ref "J5") (pin "108") (pinfunction "JTAG_MASTER_TRST_108") (pintype "passive+no_connect"))
    )
    (net (code "177") (name "unconnected-(J5B-NC-Pad99)") (class "Default")
      (node (ref "J5") (pin "99") (pinfunction "NC_99") (pintype "passive+no_connect"))
    )
    (net (code "178") (name "unconnected-(J5B-NC-Pad100)") (class "Default")
      (node (ref "J5") (pin "100") (pinfunction "NC_100") (pintype "passive+no_connect"))
    )
    (net (code "179") (name "unconnected-(J5B-NC-Pad101)") (class "Default")
      (node (ref "J5") (pin "101") (pinfunction "NC_101") (pintype "passive+no_connect"))
    )
    (net (code "180") (name "unconnected-(J6-HALT-Pad14)") (class "Default")
      (node (ref "J6") (pin "14") (pinfunction "HALT_14") (pintype "passive+no_connect"))
    )
    (net (code "181") (name "unconnected-(J6-NC-Pad12)") (class "Default")
      (node (ref "J6") (pin "12") (pinfunction "NC_12") (pintype "passive+no_connect"))
    )
    (net (code "182") (name "unconnected-(J6-ND-Pad1)") (class "Default")
      (node (ref "J6") (pin "1") (pinfunction "ND_1") (pintype "passive+no_connect"))
    )
    (net (code "183") (name "unconnected-(J6-PGND-Pad13)") (class "Default")
      (node (ref "J6") (pin "13") (pinfunction "PGND_13") (pintype "passive+no_connect"))
    )
    (net (code "184") (name "unconnected-(SW3-T2-Pad2)") (class "Default")
      (node (ref "SW3") (pin "2") (pinfunction "T2_2") (pintype "passive"))
    )
    (net (code "185") (name "unconnected-(SW3-T3-Pad3)") (class "Default")
      (node (ref "SW3") (pin "3") (pinfunction "T3_3") (pintype "passive"))
    )
    (net (code "186") (name "unconnected-(SW4-S1-Pad2)") (class "Default")
      (node (ref "SW4") (pin "2") (pinfunction "S1_2") (pintype "passive"))
    )
    (net (code "187") (name "unconnected-(SW4-S2-Pad3)") (class "Default")
      (node (ref "SW4") (pin "3") (pinfunction "S2_3") (pintype "passive"))
    )
    (net (code "188") (name "unconnected-(SW4-S3-Pad4)") (class "Default")
      (node (ref "SW4") (pin "4") (pinfunction "S3_4") (pintype "passive"))
    )
    (net (code "189") (name "unconnected-(SW4-S4C-Pad12)") (class "Default")
      (node (ref "SW4") (pin "12") (pinfunction "S4C_12") (pintype "passive"))
    )
    (net (code "190") (name "unconnected-(SW4-S5C-Pad11)") (class "Default")
      (node (ref "SW4") (pin "11") (pinfunction "S5C_11") (pintype "passive"))
    )
    (net (code "191") (name "unconnected-(SW4-S6C-Pad10)") (class "Default")
      (node (ref "SW4") (pin "10") (pinfunction "S6C_10") (pintype "passive"))
    )
  )
)
